# LampOne.net
KiCad netlist of a schematic drawn in Altium Designer
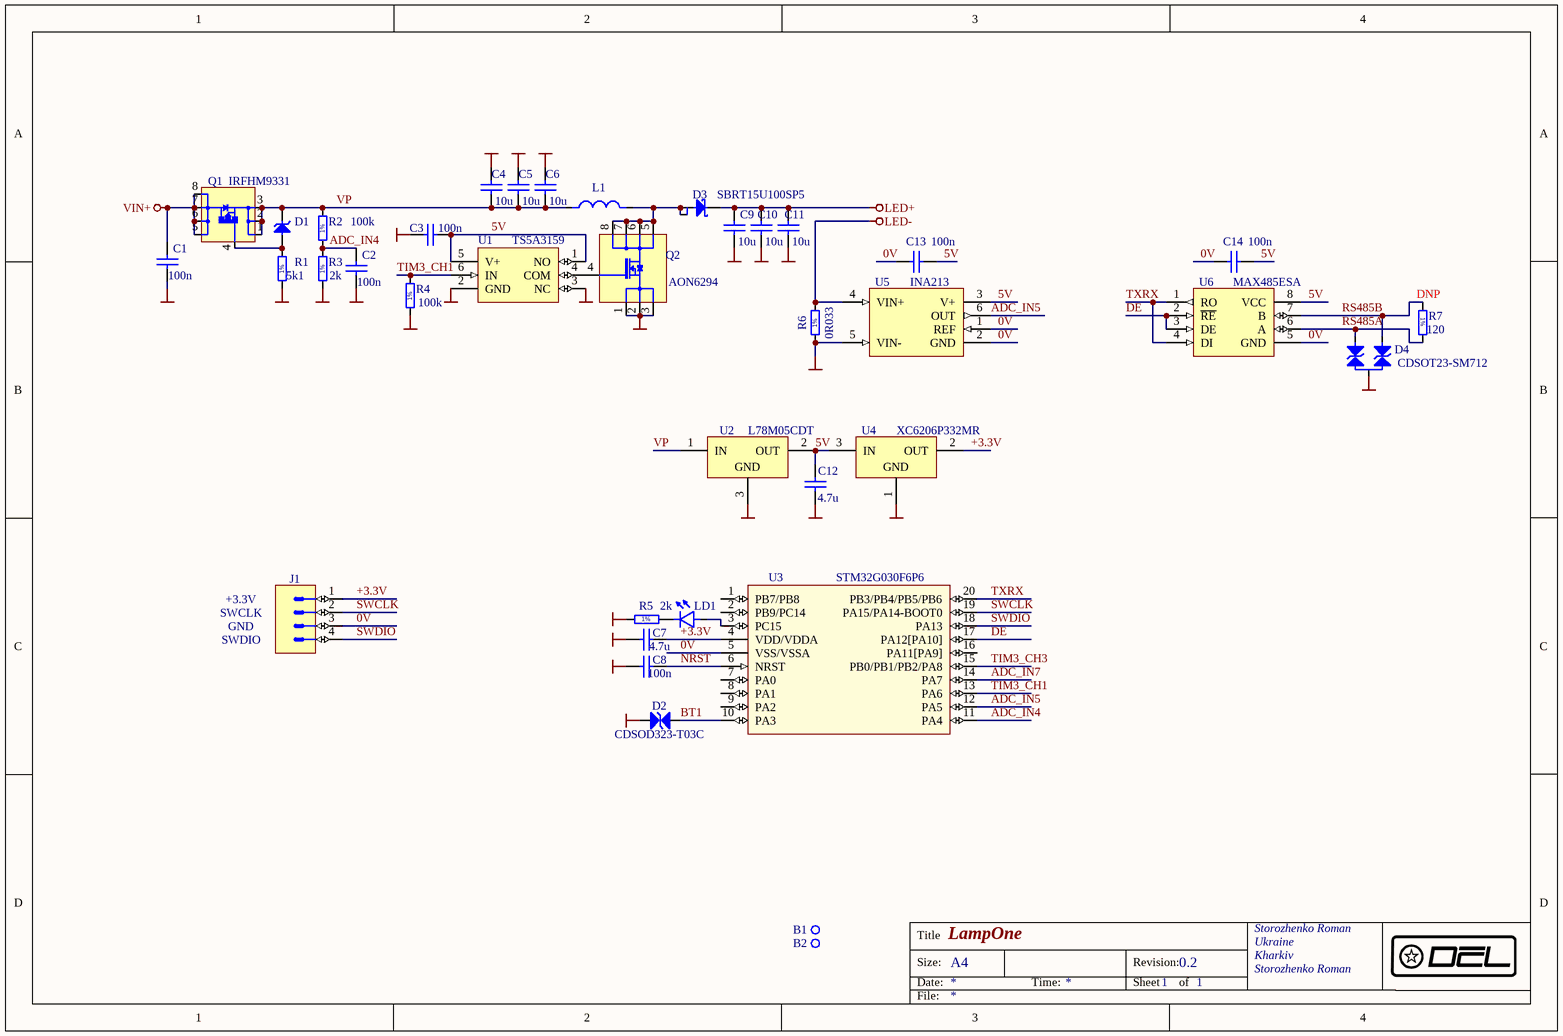
[diagram p0: LampOne.SchDoc]

(export (version "E")
  (design (tool "Eeschema 10.0.6"))
  (components
    (comp (ref "B1")
      (value "Non Plated Hole")
      (footprint "MTG600H320V8P")
      (description "Single Terminal Socket")
      (fields (field (name "PART NUMBER") "NON-PLATED_HOLE3.2_PAD6.0_8p") (field (name "AUTHOR") "DEL"))
      (libsource (lib "Eletro-mechanical") (part "Single Terminal Socket"))
    )
    (comp (ref "B2")
      (value "Non Plated Hole")
      (footprint "MTG600H320V8P")
      (description "Single Terminal Socket")
      (fields (field (name "PART NUMBER") "NON-PLATED_HOLE3.2_PAD6.0_8p") (field (name "AUTHOR") "DEL"))
      (libsource (lib "Eletro-mechanical") (part "Single Terminal Socket"))
    )
    (comp (ref "C1")
      (value "100n")
      (footprint "CAPC1608X87N")
      (description "Non-polarised capacitor")
      (fields
        (field (name "PART NUMBER") "CC0603_100NF_50V_10%_X7R")
        (field (name "VOLTAGE") "50V")
        (field (name "AUTHOR") "Elman")
      )
      (libsource (lib "Capacitors") (part "Capacitor - non polarized"))
    )
    (comp (ref "C2")
      (value "100n")
      (footprint "CAPC1608X87N")
      (description "Non-polarised capacitor")
      (fields
        (field (name "PART NUMBER") "CC0603_100NF_50V_10%_X7R")
        (field (name "VOLTAGE") "50V")
        (field (name "AUTHOR") "Elman")
      )
      (libsource (lib "Capacitors") (part "Capacitor - non polarized"))
    )
    (comp (ref "C3")
      (value "100n")
      (footprint "CAPC1608X87N")
      (description "Non-polarised capacitor")
      (fields
        (field (name "PART NUMBER") "CC0603_100NF_50V_10%_X7R")
        (field (name "VOLTAGE") "50V")
        (field (name "AUTHOR") "Elman")
      )
      (libsource (lib "Capacitors") (part "Capacitor - non polarized"))
    )
    (comp (ref "C4")
      (value "10u")
      (footprint "CAPC3225X270N")
      (description "Non-polarised capacitor")
      (fields
        (field (name "PART NUMBER") "CC1210_10UF_50V_10%_X7R")
        (field (name "VOLTAGE") "50V")
        (field (name "AUTHOR") "CERN DEM JLC")
      )
      (libsource (lib "Capacitors") (part "Capacitor - non polarized"))
    )
    (comp (ref "C5")
      (value "10u")
      (footprint "CAPC3225X270N")
      (description "Non-polarised capacitor")
      (fields
        (field (name "PART NUMBER") "CC1210_10UF_50V_10%_X7R")
        (field (name "VOLTAGE") "50V")
        (field (name "AUTHOR") "CERN DEM JLC")
      )
      (libsource (lib "Capacitors") (part "Capacitor - non polarized"))
    )
    (comp (ref "C6")
      (value "10u")
      (footprint "CAPC3225X270N")
      (description "Non-polarised capacitor")
      (fields
        (field (name "PART NUMBER") "CC1210_10UF_50V_10%_X7R")
        (field (name "VOLTAGE") "50V")
        (field (name "AUTHOR") "CERN DEM JLC")
      )
      (libsource (lib "Capacitors") (part "Capacitor - non polarized"))
    )
    (comp (ref "C7")
      (value "4.7u")
      (footprint "CAPC1608X87N")
      (description "Non-polarised capacitor")
      (fields
        (field (name "PART NUMBER") "CC0603_4.7UF_10V_10%_X5R")
        (field (name "VOLTAGE") "10V")
        (field (name "AUTHOR") "ELMAN")
      )
      (libsource (lib "Capacitors") (part "Capacitor - non polarized"))
    )
    (comp (ref "C8")
      (value "100n")
      (footprint "CAPC1608X87N")
      (description "Non-polarised capacitor")
      (fields
        (field (name "PART NUMBER") "CC0603_100NF_50V_10%_X7R")
        (field (name "VOLTAGE") "50V")
        (field (name "AUTHOR") "Elman")
      )
      (libsource (lib "Capacitors") (part "Capacitor - non polarized"))
    )
    (comp (ref "C9")
      (value "10u")
      (footprint "CAPC3225X270N")
      (description "Non-polarised capacitor")
      (fields
        (field (name "PART NUMBER") "CC1210_10UF_50V_10%_X7R")
        (field (name "VOLTAGE") "50V")
        (field (name "AUTHOR") "CERN DEM JLC")
      )
      (libsource (lib "Capacitors") (part "Capacitor - non polarized"))
    )
    (comp (ref "C10")
      (value "10u")
      (footprint "CAPC3225X270N")
      (description "Non-polarised capacitor")
      (fields
        (field (name "PART NUMBER") "CC1210_10UF_50V_10%_X7R")
        (field (name "VOLTAGE") "50V")
        (field (name "AUTHOR") "CERN DEM JLC")
      )
      (libsource (lib "Capacitors") (part "Capacitor - non polarized"))
    )
    (comp (ref "C11")
      (value "10u")
      (footprint "CAPC3225X270N")
      (description "Non-polarised capacitor")
      (fields
        (field (name "PART NUMBER") "CC1210_10UF_50V_10%_X7R")
        (field (name "VOLTAGE") "50V")
        (field (name "AUTHOR") "CERN DEM JLC")
      )
      (libsource (lib "Capacitors") (part "Capacitor - non polarized"))
    )
    (comp (ref "C12")
      (value "4.7u")
      (footprint "CAPC1608X87N")
      (description "Non-polarised capacitor")
      (fields
        (field (name "PART NUMBER") "CC0603_4.7UF_10V_10%_X5R")
        (field (name "VOLTAGE") "10V")
        (field (name "AUTHOR") "ELMAN")
      )
      (libsource (lib "Capacitors") (part "Capacitor - non polarized"))
    )
    (comp (ref "C13")
      (value "100n")
      (footprint "CAPC1608X87N")
      (description "Non-polarised capacitor")
      (fields
        (field (name "PART NUMBER") "CC0603_100NF_50V_10%_X7R")
        (field (name "VOLTAGE") "50V")
        (field (name "AUTHOR") "Elman")
      )
      (libsource (lib "Capacitors") (part "Capacitor - non polarized"))
    )
    (comp (ref "C14")
      (value "100n")
      (footprint "CAPC1608X87N")
      (description "Non-polarised capacitor")
      (fields
        (field (name "PART NUMBER") "CC0603_100NF_50V_10%_X7R")
        (field (name "VOLTAGE") "50V")
        (field (name "AUTHOR") "Elman")
      )
      (libsource (lib "Capacitors") (part "Capacitor - non polarized"))
    )
    (comp (ref "D1")
      (value "BZV55-B10")
      (footprint "DIOMELF3515N")
      (description "Zener Diode")
      (fields
        (field (name "VOLTAGE") "10V")
        (field (name "POWER") "500mW")
        (field (name "AUTHOR") "CERN DEM JLC")
      )
      (libsource (lib "ICs And Semiconductors") (part "Diode Zener"))
    )
    (comp (ref "D2")
      (value "CDSOD323-T03C")
      (footprint "SOD2512X110N")
      (description "Transient Voltage Suppressor Diode (Bi-Directional)")
      (fields (field (name "VOLTAGE") "4V") (field (name "POWER") "20A") (field (name "AUTHOR") "DEL"))
      (libsource (lib "ICs And Semiconductors") (part "Diode TVS Bi-Directional"))
    )
    (comp (ref "D3")
      (value "SBRT15U100SP5")
      (footprint "SBRT15U100SP5")
      (description "Diode  Schottky Anode pin 1 and 2 cathode pin 3")
      (fields (field (name "VOLTAGE") "100V") (field (name "POWER") "15A") (field (name "AUTHOR") "DEL"))
      (libsource (lib "ICs And Semiconductors") (part "Diode Schottky A1A2_C3"))
    )
    (comp (ref "D4")
      (value "CDSOT23-SM712")
      (footprint "SOT95P240X130-3N")
      (description "Transient Voltage Suppressor Diode (Bi-Directional)")
      (fields (field (name "VOLTAGE") "7.5V") (field (name "POWER") "17A") (field (name "AUTHOR") "DEL"))
      (libsource (lib "ICs And Semiconductors") (part "Diode TVS Bi-Directional x2"))
    )
    (comp (ref "J1")
      (value "Header 4")
      (footprint "3M_2304-6111-TG")
      (description "Connector 4 Male")
      (fields
        (field (name "PART NUMBER") "3M_2304-6111-TG")
        (field (name "MANUFACTURER") "3M")
        (field (name "AUTHOR") "DEL")
      )
      (libsource (lib "Connectors") (part "Connector 4 Male"))
    )
    (comp (ref "L1")
      (value "10uH")
      (footprint "IND_BOURNS_PM127SH")
      (description "Inductor")
      (fields
        (field (name "PART NUMBER") "IND_10UH_20%_SUMIDA_CDRH125")
        (field (name "POWER") "4A")
        (field (name "AUTHOR") "CERN DEM JLC")
      )
      (libsource (lib "Inductors & Transformers") (part "Inductor"))
    )
    (comp (ref "LD1")
      (value "Red")
      (footprint "LEDC1608X80N_RED")
      (description "LED 1C 2A")
      (fields
        (field (name "PART NUMBER") "LED_ROHM_SML-311UTT86K")
        (field (name "MANUFACTURER") "ROHM")
        (field (name "AUTHOR") "CERN DEM JLC")
      )
      (libsource (lib "ICs And Semiconductors") (part "LED 1C 2A"))
    )
    (comp (ref "Q1")
      (value "IRFHM9331")
      (footprint "PQFN50P300X300X100_HS-9N")
      (description "P-CHANNEL MOSFET WITH DIODE")
      (fields
        (field (name "PART NUMBER") "IRFHM9331TRPbF")
        (field (name "MANUFACTURER") "INFINEON")
        (field (name "AUTHOR") "DEL")
      )
      (libsource (lib "ICs And Semiconductors") (part "P-MOSFET-D 1-3S 4G 5-8D"))
    )
    (comp (ref "Q2")
      (value "AON6294")
      (footprint "DFN-5X6-8L")
      (fields (field (name "MANUFACTURER") "LPHA & OMEGA SEMICONDUCTOR") (field (name "AUTHOR") "DEL"))
      (libsource (lib "ICs And Semiconductors") (part "N-MOSFET-D 1-3S 4G 5-8D"))
    )
    (comp (ref "R1")
      (value "5k1")
      (footprint "RESC1608X55N")
      (description "Resistor - 1%")
      (fields
        (field (name "PART NUMBER") "R0603_5K1_1%_0.1W_100PPM")
        (field (name "POWER") "0.1W")
        (field (name "AUTHOR") "CERN DEM JLC")
      )
      (libsource (lib "Resistors") (part "Resistor - 1%"))
    )
    (comp (ref "R2")
      (value "100k")
      (footprint "RESC1608X55N")
      (description "Resistor - 1%")
      (fields
        (field (name "PART NUMBER") "R0603_100K_1%_0.1W_100PPM")
        (field (name "POWER") "0.1W")
        (field (name "AUTHOR") "CERN DEM JLC")
      )
      (libsource (lib "Resistors") (part "Resistor - 1%"))
    )
    (comp (ref "R3")
      (value "2k")
      (footprint "RESC1608X55N")
      (description "Resistor - 1%")
      (fields
        (field (name "PART NUMBER") "R0603_2K_1%_0.1W_100PPM")
        (field (name "POWER") "0.1W")
        (field (name "AUTHOR") "CERN DEM JLC")
      )
      (libsource (lib "Resistors") (part "Resistor - 1%"))
    )
    (comp (ref "R4")
      (value "100k")
      (footprint "RESC1608X55N")
      (description "Resistor - 1%")
      (fields
        (field (name "PART NUMBER") "R0603_100K_1%_0.1W_100PPM")
        (field (name "POWER") "0.1W")
        (field (name "AUTHOR") "CERN DEM JLC")
      )
      (libsource (lib "Resistors") (part "Resistor - 1%"))
    )
    (comp (ref "R5")
      (value "2k")
      (footprint "RESC1608X55N")
      (description "Resistor - 1%")
      (fields
        (field (name "PART NUMBER") "R0603_2K_1%_0.1W_100PPM")
        (field (name "POWER") "0.1W")
        (field (name "AUTHOR") "CERN DEM JLC")
      )
      (libsource (lib "Resistors") (part "Resistor - 1%"))
    )
    (comp (ref "R6")
      (value "0R033")
      (footprint "RESC3216X80N")
      (description "Resistor - 1%")
      (fields
        (field (name "PART NUMBER") "R1206_0R033_1%_0.25W_100PPM")
        (field (name "POWER") "0.25W")
        (field (name "AUTHOR") "DEL")
      )
      (libsource (lib "Resistors") (part "Resistor - 1%"))
    )
    (comp (ref "R7")
      (value "120")
      (footprint "RESC1005X40N")
      (description "Resistor - 1%")
      (fields
        (field (name "PART NUMBER") "R0402_120R_1%_0.0625W_100PPM")
        (field (name "POWER") "0.0625W")
        (field (name "MOUNTED") "DNP")
        (field (name "AUTHOR") "CERN DEM JLC")
      )
      (libsource (lib "Resistors") (part "Resistor - 1%"))
    )
    (comp (ref "U1")
      (value "TS5A3159")
      (footprint "SOT65P210X110-6N")
      (description "1-Ω SPDT Analog Switch")
      (fields
        (field (name "PART NUMBER") "TS5A3159DCKR")
        (field (name "MANUFACTURER") "TEXAS INSTRUMENTS")
        (field (name "AUTHOR") "DEL")
      )
      (libsource (lib "ICs And Semiconductors") (part "TS5A3159"))
    )
    (comp (ref "U2")
      (value "L78M05CDT")
      (footprint "TO228P1010X239-3N-R521X544")
      (description "3-Terminal Regulator 1=IN 2=OUT 3=GND")
      (fields
        (field (name "PART NUMBER") "L78M05CDT-TR")
        (field (name "MANUFACTURER") "ST MICROELECTRONICS")
        (field (name "AUTHOR") "DEL")
      )
      (libsource (lib "ICs And Semiconductors") (part "REG3 1IN-2OUT-3GND"))
    )
    (comp (ref "U3")
      (value "STM32G030F6P6")
      (footprint "SOP65P640X110-20N")
      (description "Arm® Cortex®-M0+ 32-bit MCU")
      (fields
        (field (name "MANUFACTURER") "ST Microelectronics")
        (field (name "MANUFACTURER PART NUMBER") "STM32F030F4P6")
        (field (name "AUTHOR") "DEL")
      )
      (libsource (lib "ICs And Semiconductors") (part "STM32G030x6"))
    )
    (comp (ref "U4")
      (value "XC6206P332MR")
      (footprint "SOT95P280X115-3N")
      (description "3-Terminal Regulator 1=GND 2=OUT 3=IN")
      (fields
        (field (name "MANUFACTURER") "TOREX")
        (field (name "MANUFACTURER PART NUMBER") "SOT95P280X115-3N")
        (field (name "AUTHOR") "DEL")
      )
      (libsource (lib "ICs And Semiconductors") (part "REG3 1GND-2OUT-3IN"))
    )
    (comp (ref "U5")
      (value "INA213")
      (footprint "SOT65P210X110-6N")
      (fields
        (field (name "PART NUMBER") "INA213xID")
        (field (name "MANUFACTURER") "TEXAS INSTRUMENTS")
        (field (name "MANUFACTURER PART NUMBER") "INA213AIDCKT")
        (field (name "AUTHOR") "DEL")
      )
      (libsource (lib "ICs And Semiconductors") (part "INA213"))
    )
    (comp (ref "U6")
      (value "MAX485ESA")
      (footprint "SOIC127P600X175-8N")
      (description "Low-Power, Slew-Rate-Limited\r\nRS-485/RS-422 Transceivers")
      (fields (field (name "MANUFACTURER") "MAXIM") (field (name "AUTHOR") "DEL"))
      (libsource (lib "ICs And Semiconductors") (part "MAX48x"))
    )
  )
  (nets
    (net (code "1") (name "/+3.3V") (class "Default")
      (node (ref "C7") (pin "2") (pinfunction "2_2") (pintype "passive"))
      (node (ref "J1") (pin "1") (pinfunction "1_1") (pintype "bidirectional"))
      (node (ref "U3") (pin "4") (pinfunction "VDD/VDDA_4") (pintype "power_in"))
      (node (ref "U4") (pin "2") (pinfunction "OUT_2") (pintype "power_in"))
    )
    (net (code "2") (name "/5V") (class "Default")
      (node (ref "C12") (pin "2") (pinfunction "2_2") (pintype "passive"))
      (node (ref "C13") (pin "1") (pinfunction "1_1") (pintype "passive"))
      (node (ref "C14") (pin "1") (pinfunction "1_1") (pintype "passive"))
      (node (ref "C3") (pin "1") (pinfunction "1_1") (pintype "passive"))
      (node (ref "U1") (pin "1") (pinfunction "NO_1") (pintype "bidirectional"))
      (node (ref "U1") (pin "5") (pinfunction "V+_5") (pintype "power_in"))
      (node (ref "U2") (pin "2") (pinfunction "OUT_2") (pintype "power_in"))
      (node (ref "U4") (pin "3") (pinfunction "IN_3") (pintype "power_in"))
      (node (ref "U5") (pin "3") (pinfunction "V+_3") (pintype "power_in"))
      (node (ref "U6") (pin "8") (pinfunction "VCC_8") (pintype "power_in"))
    )
    (net (code "3") (name "/ADC_IN4") (class "Default")
      (node (ref "C2") (pin "2") (pinfunction "2_2") (pintype "passive"))
      (node (ref "R2") (pin "1") (pinfunction "1_1") (pintype "passive"))
      (node (ref "R3") (pin "2") (pinfunction "2_2") (pintype "passive"))
      (node (ref "U3") (pin "11") (pinfunction "PA4_11") (pintype "bidirectional"))
    )
    (net (code "4") (name "/ADC_IN5") (class "Default")
      (node (ref "U3") (pin "12") (pinfunction "PA5_12") (pintype "bidirectional"))
      (node (ref "U5") (pin "6") (pinfunction "OUT_6") (pintype "output"))
    )
    (net (code "5") (name "/ADC_IN7") (class "Default")
      (node (ref "U3") (pin "14") (pinfunction "PA7_14") (pintype "bidirectional"))
    )
    (net (code "6") (name "/BT1") (class "Default")
      (node (ref "D2") (pin "1") (pinfunction "C_1") (pintype "passive"))
      (node (ref "U3") (pin "10") (pinfunction "PA3_10") (pintype "bidirectional"))
    )
    (net (code "7") (name "/DE") (class "Default")
      (node (ref "U3") (pin "17") (pinfunction "PA12[PA10]_17") (pintype "bidirectional"))
      (node (ref "U6") (pin "2") (pinfunction "~{RE}_2") (pintype "input"))
      (node (ref "U6") (pin "3") (pinfunction "DE_3") (pintype "input"))
    )
    (net (code "8") (name "/NRST") (class "Default")
      (node (ref "C8") (pin "2") (pinfunction "2_2") (pintype "passive"))
      (node (ref "U3") (pin "6") (pinfunction "NRST_6") (pintype "input"))
    )
    (net (code "9") (name "/RS485A") (class "Default")
      (node (ref "D4") (pin "2") (pinfunction "2_2") (pintype "passive"))
      (node (ref "R7") (pin "2") (pinfunction "2_2") (pintype "passive"))
      (node (ref "U6") (pin "6") (pinfunction "A_6") (pintype "bidirectional"))
    )
    (net (code "10") (name "/RS485B") (class "Default")
      (node (ref "D4") (pin "1") (pinfunction "1_1") (pintype "passive"))
      (node (ref "R7") (pin "1") (pinfunction "1_1") (pintype "passive"))
      (node (ref "U6") (pin "7") (pinfunction "B_7") (pintype "bidirectional"))
    )
    (net (code "11") (name "/SWCLK") (class "Default")
      (node (ref "J1") (pin "2") (pinfunction "2_2") (pintype "bidirectional"))
      (node (ref "U3") (pin "19") (pinfunction "PA15/PA14-BOOT0_19") (pintype "bidirectional"))
    )
    (net (code "12") (name "/SWDIO") (class "Default")
      (node (ref "J1") (pin "4") (pinfunction "4_4") (pintype "bidirectional"))
      (node (ref "U3") (pin "18") (pinfunction "PA13_18") (pintype "bidirectional"))
    )
    (net (code "13") (name "/TIM3_CH1") (class "Default")
      (node (ref "R4") (pin "2") (pinfunction "2_2") (pintype "passive"))
      (node (ref "U1") (pin "6") (pinfunction "IN_6") (pintype "input"))
      (node (ref "U3") (pin "13") (pinfunction "PA6_13") (pintype "bidirectional"))
    )
    (net (code "14") (name "/TIM3_CH3") (class "Default")
      (node (ref "U3") (pin "15") (pinfunction "PB0/PB1/PB2/PA8_15") (pintype "bidirectional"))
    )
    (net (code "15") (name "/TXRX") (class "Default")
      (node (ref "U3") (pin "20") (pinfunction "PB3/PB4/PB5/PB6_20") (pintype "bidirectional"))
      (node (ref "U6") (pin "1") (pinfunction "RO_1") (pintype "output"))
      (node (ref "U6") (pin "4") (pinfunction "DI_4") (pintype "input"))
    )
    (net (code "16") (name "/VP") (class "Default")
      (node (ref "C4") (pin "2") (pinfunction "2_2") (pintype "passive"))
      (node (ref "C5") (pin "2") (pinfunction "2_2") (pintype "passive"))
      (node (ref "C6") (pin "2") (pinfunction "2_2") (pintype "passive"))
      (node (ref "D1") (pin "1") (pinfunction "C_1") (pintype "passive"))
      (node (ref "L1") (pin "1") (pinfunction "1_1") (pintype "passive"))
      (node (ref "Q1") (pin "1") (pinfunction "S_1") (pintype "passive"))
      (node (ref "Q1") (pin "2") (pinfunction "S_2") (pintype "passive"))
      (node (ref "Q1") (pin "3") (pinfunction "S_3") (pintype "passive"))
      (node (ref "R2") (pin "2") (pinfunction "2_2") (pintype "passive"))
      (node (ref "U2") (pin "1") (pinfunction "IN_1") (pintype "power_in"))
    )
    (net (code "17") (name "0V") (class "Default")
      (node (ref "C1") (pin "1") (pinfunction "1_1") (pintype "passive"))
      (node (ref "C10") (pin "1") (pinfunction "1_1") (pintype "passive"))
      (node (ref "C11") (pin "1") (pinfunction "1_1") (pintype "passive"))
      (node (ref "C12") (pin "1") (pinfunction "1_1") (pintype "passive"))
      (node (ref "C13") (pin "2") (pinfunction "2_2") (pintype "passive"))
      (node (ref "C14") (pin "2") (pinfunction "2_2") (pintype "passive"))
      (node (ref "C2") (pin "1") (pinfunction "1_1") (pintype "passive"))
      (node (ref "C3") (pin "2") (pinfunction "2_2") (pintype "passive"))
      (node (ref "C4") (pin "1") (pinfunction "1_1") (pintype "passive"))
      (node (ref "C5") (pin "1") (pinfunction "1_1") (pintype "passive"))
      (node (ref "C6") (pin "1") (pinfunction "1_1") (pintype "passive"))
      (node (ref "C7") (pin "1") (pinfunction "1_1") (pintype "passive"))
      (node (ref "C8") (pin "1") (pinfunction "1_1") (pintype "passive"))
      (node (ref "C9") (pin "1") (pinfunction "1_1") (pintype "passive"))
      (node (ref "D2") (pin "2") (pinfunction "A_2") (pintype "passive"))
      (node (ref "D4") (pin "3") (pinfunction "3_3") (pintype "passive"))
      (node (ref "J1") (pin "3") (pinfunction "3_3") (pintype "bidirectional"))
      (node (ref "Q2") (pin "1") (pinfunction "S_1") (pintype "passive"))
      (node (ref "Q2") (pin "2") (pinfunction "S_2") (pintype "passive"))
      (node (ref "Q2") (pin "3") (pinfunction "S_3") (pintype "passive"))
      (node (ref "R1") (pin "1") (pinfunction "1_1") (pintype "passive"))
      (node (ref "R3") (pin "1") (pinfunction "1_1") (pintype "passive"))
      (node (ref "R4") (pin "1") (pinfunction "1_1") (pintype "passive"))
      (node (ref "R5") (pin "1") (pinfunction "1_1") (pintype "passive"))
      (node (ref "R6") (pin "1") (pinfunction "1_1") (pintype "passive"))
      (node (ref "U1") (pin "2") (pinfunction "GND_2") (pintype "power_in"))
      (node (ref "U1") (pin "3") (pinfunction "NC_3") (pintype "bidirectional"))
      (node (ref "U2") (pin "3") (pinfunction "GND_3") (pintype "power_in"))
      (node (ref "U3") (pin "5") (pinfunction "VSS/VSSA_5") (pintype "power_in"))
      (node (ref "U4") (pin "1") (pinfunction "GND_1") (pintype "power_in"))
      (node (ref "U5") (pin "1") (pinfunction "REF_1") (pintype "input"))
      (node (ref "U5") (pin "2") (pinfunction "GND_2") (pintype "power_in"))
      (node (ref "U5") (pin "5") (pinfunction "VIN-_5") (pintype "input"))
      (node (ref "U6") (pin "5") (pinfunction "GND_5") (pintype "power_in"))
    )
    (net (code "18") (name "LED+") (class "Default")
      (node (ref "C10") (pin "2") (pinfunction "2_2") (pintype "passive"))
      (node (ref "C11") (pin "2") (pinfunction "2_2") (pintype "passive"))
      (node (ref "C9") (pin "2") (pinfunction "2_2") (pintype "passive"))
      (node (ref "D3") (pin "3") (pinfunction "C_3") (pintype "passive"))
    )
    (net (code "19") (name "LED-") (class "Default")
      (node (ref "R6") (pin "2") (pinfunction "2_2") (pintype "passive"))
      (node (ref "U5") (pin "4") (pinfunction "VIN+_4") (pintype "input"))
    )
    (net (code "20") (name "Net-(D1-A)") (class "Default")
      (node (ref "D1") (pin "2") (pinfunction "A_2") (pintype "passive"))
      (node (ref "Q1") (pin "4") (pinfunction "S_4") (pintype "passive"))
      (node (ref "R1") (pin "2") (pinfunction "2_2") (pintype "passive"))
    )
    (net (code "21") (name "Net-(D3-A-Pad1)") (class "Default")
      (node (ref "D3") (pin "1") (pinfunction "A_1") (pintype "passive"))
      (node (ref "D3") (pin "2") (pinfunction "A_2") (pintype "passive"))
      (node (ref "L1") (pin "2") (pinfunction "2_2") (pintype "passive"))
      (node (ref "Q2") (pin "5") (pinfunction "D_5") (pintype "passive"))
      (node (ref "Q2") (pin "6") (pinfunction "D_6") (pintype "passive"))
      (node (ref "Q2") (pin "7") (pinfunction "D_7") (pintype "passive"))
      (node (ref "Q2") (pin "8") (pinfunction "D_8") (pintype "passive"))
    )
    (net (code "22") (name "Net-(LD1-A)") (class "Default")
      (node (ref "LD1") (pin "2") (pinfunction "A_2") (pintype "passive"))
      (node (ref "U3") (pin "3") (pinfunction "PC15_3") (pintype "bidirectional"))
    )
    (net (code "23") (name "Net-(LD1-C)") (class "Default")
      (node (ref "LD1") (pin "1") (pinfunction "C_1") (pintype "passive"))
      (node (ref "R5") (pin "2") (pinfunction "2_2") (pintype "passive"))
    )
    (net (code "24") (name "Net-(Q2-G)") (class "Default")
      (node (ref "Q2") (pin "4") (pinfunction "G_4") (pintype "passive"))
      (node (ref "U1") (pin "4") (pinfunction "COM_4") (pintype "bidirectional"))
    )
    (net (code "25") (name "VIN+") (class "Default")
      (node (ref "C1") (pin "2") (pinfunction "2_2") (pintype "passive"))
      (node (ref "Q1") (pin "5") (pinfunction "D_5") (pintype "passive"))
      (node (ref "Q1") (pin "6") (pinfunction "D_6") (pintype "passive"))
      (node (ref "Q1") (pin "7") (pinfunction "D_7") (pintype "passive"))
      (node (ref "Q1") (pin "8") (pinfunction "D_8") (pintype "passive"))
    )
    (net (code "26") (name "unconnected-(B1-Pad1)") (class "Default")
      (node (ref "B1") (pin "1") (pinfunction "1_1") (pintype "bidirectional"))
    )
    (net (code "27") (name "unconnected-(B2-Pad1)") (class "Default")
      (node (ref "B2") (pin "1") (pinfunction "1_1") (pintype "bidirectional"))
    )
    (net (code "28") (name "unconnected-(U3-PA0-Pad7)") (class "Default")
      (node (ref "U3") (pin "7") (pinfunction "PA0_7") (pintype "bidirectional"))
    )
    (net (code "29") (name "unconnected-(U3-PA1-Pad8)") (class "Default")
      (node (ref "U3") (pin "8") (pinfunction "PA1_8") (pintype "bidirectional"))
    )
    (net (code "30") (name "unconnected-(U3-PA2-Pad9)") (class "Default")
      (node (ref "U3") (pin "9") (pinfunction "PA2_9") (pintype "bidirectional"))
    )
    (net (code "31") (name "unconnected-(U3-PA11[PA9]-Pad16)") (class "Default")
      (node (ref "U3") (pin "16") (pinfunction "PA11[PA9]_16") (pintype "bidirectional"))
    )
    (net (code "32") (name "unconnected-(U3-PB7{slash}PB8-Pad1)") (class "Default")
      (node (ref "U3") (pin "1") (pinfunction "PB7/PB8_1") (pintype "bidirectional"))
    )
    (net (code "33") (name "unconnected-(U3-PB9{slash}PC14-Pad2)") (class "Default")
      (node (ref "U3") (pin "2") (pinfunction "PB9/PC14_2") (pintype "bidirectional"))
    )
  )
)
